# Solar_Charger_Shield_v2_2.net
KiCad netlist of a schematic drawn in EAGLE
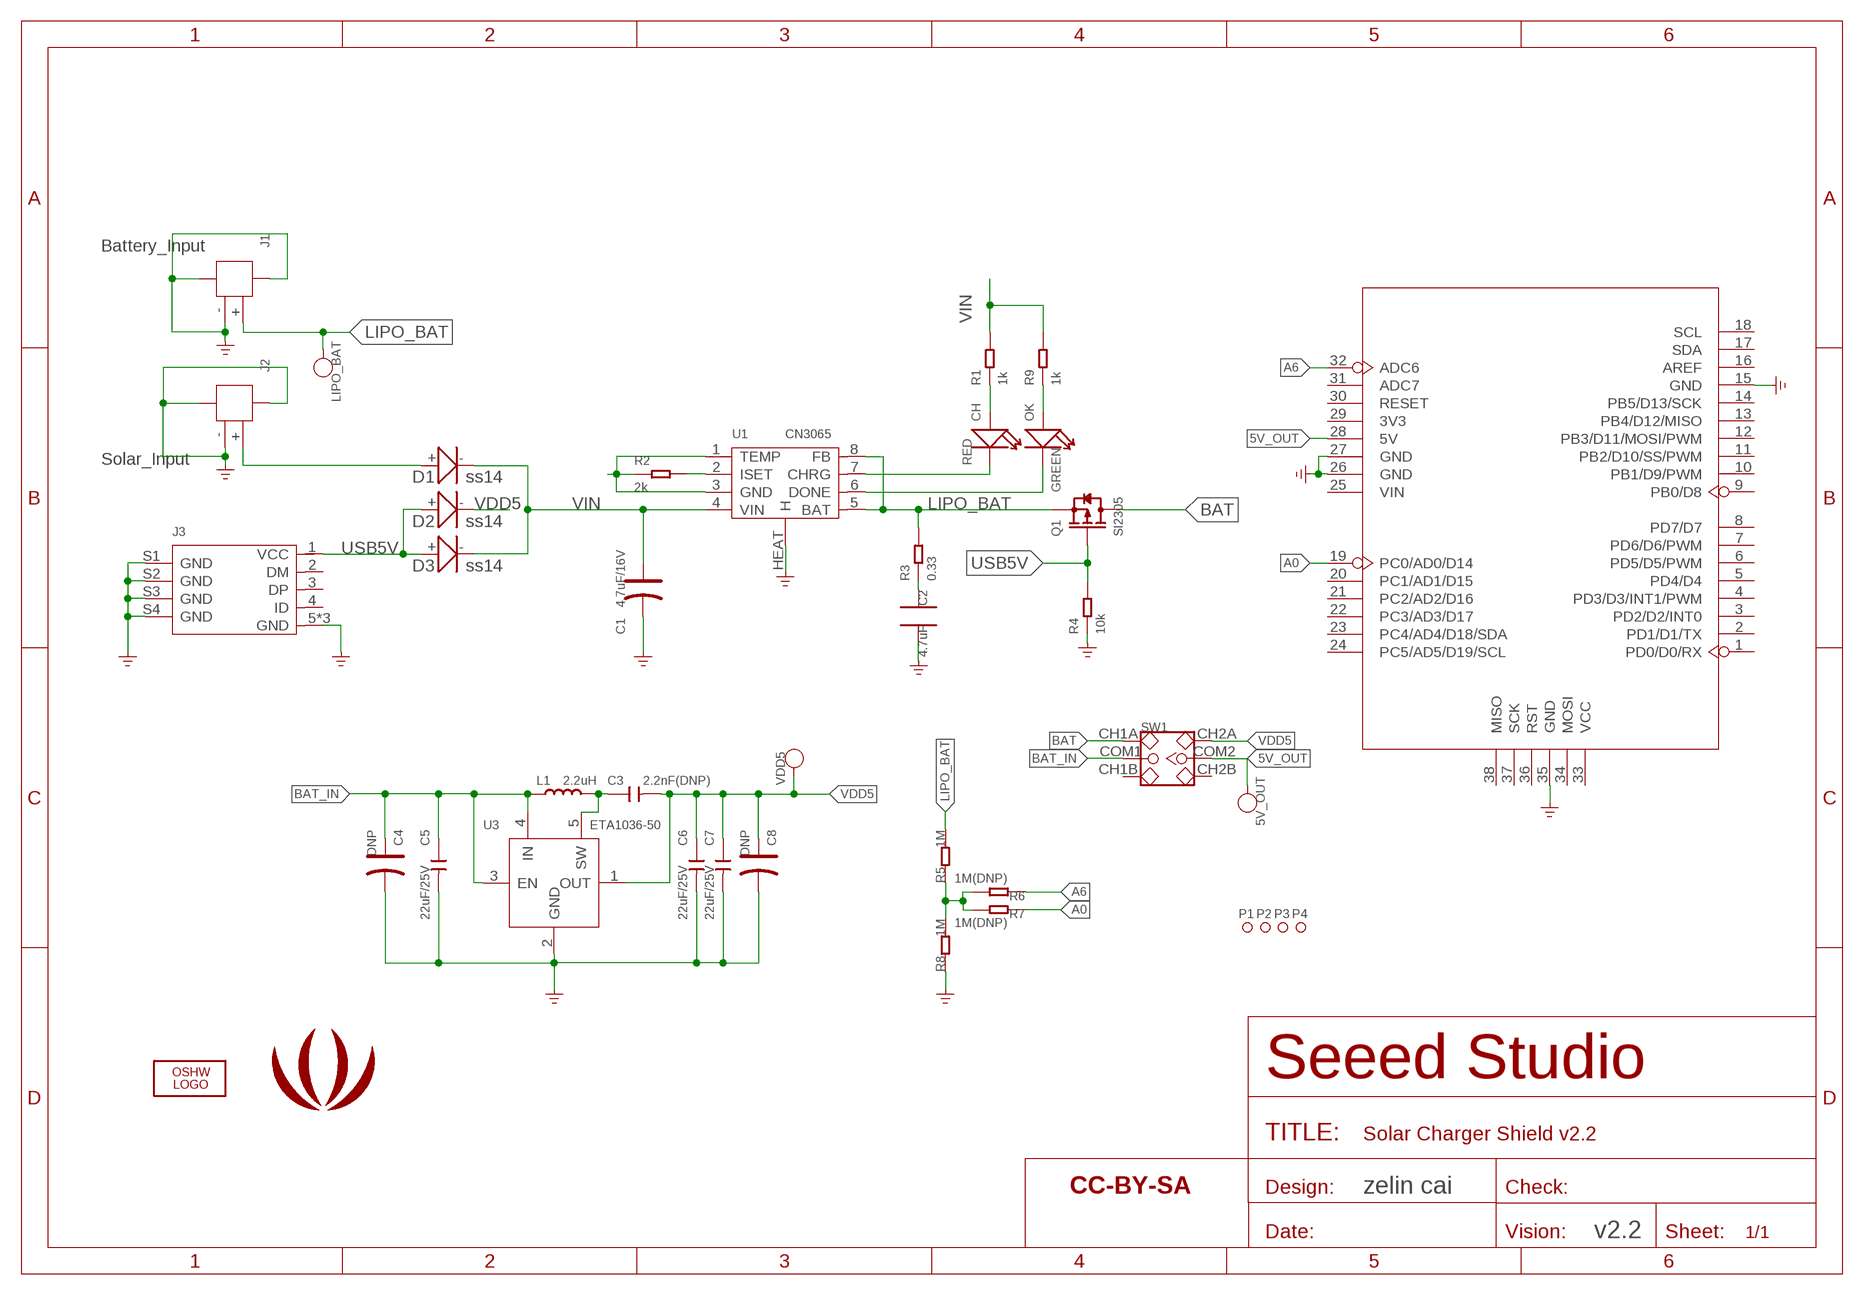
[diagram p0: schematic, sheet 1]

(export (version "E")
  (design (tool "Eeschema 10.0.6"))
  (components
    (comp (ref "5V_OUT")
      (value "PAD-TEST-POINT'4545'")
      (footprint "eagle-import:TP-D45MIL")
      (fields (field (name "PARTNO") "DNP"))
      (libsource (lib "eagle-import") (part "PAD-TEST-POINT'4545'"))
    )
    (comp (ref "C1")
      (value "4.7uF/16V")
      (footprint "eagle-import:AVX_A")
      (libsource (lib "eagle-import") (part "006-CAP_AVX_A"))
    )
    (comp (ref "C2")
      (value "4.7uF")
      (footprint "eagle-import:0805")
      (libsource (lib "eagle-import") (part "C0805"))
    )
    (comp (ref "C3")
      (value "2.2nF(DNP)")
      (footprint "eagle-import:C0603")
      (libsource (lib "eagle-import") (part "C-0603"))
    )
    (comp (ref "C4")
      (value "DNP")
      (footprint "eagle-import:AVX-A")
      (libsource (lib "eagle-import") (part "CAP_AVX_A"))
    )
    (comp (ref "C5")
      (value "22uF/25V")
      (footprint "eagle-import:C0805")
      (libsource (lib "eagle-import") (part "CAP-0805"))
    )
    (comp (ref "C6")
      (value "22uF/25V")
      (footprint "eagle-import:C0805")
      (libsource (lib "eagle-import") (part "CAP-0805"))
    )
    (comp (ref "C7")
      (value "22uF/25V")
      (footprint "eagle-import:C0805")
      (libsource (lib "eagle-import") (part "CAP-0805"))
    )
    (comp (ref "C8")
      (value "DNP")
      (footprint "eagle-import:AVX-A")
      (libsource (lib "eagle-import") (part "CAP_AVX_A"))
    )
    (comp (ref "CH")
      (value "RED")
      (footprint "eagle-import:LED-0603")
      (libsource (lib "eagle-import") (part "LED'0603'"))
    )
    (comp (ref "D1")
      (value "ss14")
      (footprint "eagle-import:D2010")
      (libsource (lib "eagle-import") (part "010-D2010"))
    )
    (comp (ref "D2")
      (value "ss14")
      (footprint "eagle-import:D2010")
      (libsource (lib "eagle-import") (part "010-D2010"))
    )
    (comp (ref "D3")
      (value "ss14")
      (footprint "eagle-import:D2010")
      (libsource (lib "eagle-import") (part "010-D2010"))
    )
    (comp (ref "J1")
      (value "JST-2P-SMD'2.0'")
      (footprint "eagle-import:2P-SMD-2.0-90D")
      (libsource (lib "eagle-import") (part "JST-2P-SMD'2.0'"))
    )
    (comp (ref "J2")
      (value "JST-2P-SMD'2.0'")
      (footprint "eagle-import:2P-SMD-2.0-90D")
      (libsource (lib "eagle-import") (part "JST-2P-SMD'2.0'"))
    )
    (comp (ref "J3")
      (value "USB-MICRO-5P'5+4P'")
      (footprint "eagle-import:5+4P-SMD-0.65-B")
      (libsource (lib "eagle-import") (part "USB-MICRO-5P'5+4P'"))
    )
    (comp (ref "L1")
      (value "2.2uH")
      (footprint "eagle-import:L0630")
      (libsource (lib "eagle-import") (part "INDUCTOR/FERRITE-BEAD'0630'"))
    )
    (comp (ref "LIPO_BAT")
      (value "PAD-TEST-POINT'4545'")
      (footprint "eagle-import:TP-D45MIL")
      (fields (field (name "PARTNO") "DNP"))
      (libsource (lib "eagle-import") (part "PAD-TEST-POINT'4545'"))
    )
    (comp (ref "LOGO1")
      (value "LOGO-OSHW-FILLX0200-NT")
      (footprint "eagle-import:OSHW_FILLX200_NOTEXT")
      (fields (field (name "PARTNO") "DNP"))
      (libsource (lib "eagle-import") (part "LOGO-OSHW-FILLX0200-NT"))
    )
    (comp (ref "OK")
      (value "GREEN")
      (footprint "eagle-import:LED-0603")
      (libsource (lib "eagle-import") (part "LED'0603'"))
    )
    (comp (ref "P1")
      (value "PAD-MARK'ANNULAR'")
      (footprint "eagle-import:ROUND-MARK-1.0")
      (fields (field (name "PARTNO") "DNP"))
      (libsource (lib "eagle-import") (part "PAD-MARK'ANNULAR'"))
    )
    (comp (ref "P2")
      (value "PAD-MARK'ANNULAR'")
      (footprint "eagle-import:ROUND-MARK-1.0")
      (fields (field (name "PARTNO") "DNP"))
      (libsource (lib "eagle-import") (part "PAD-MARK'ANNULAR'"))
    )
    (comp (ref "P3")
      (value "PAD-MARK'ANNULAR'")
      (footprint "eagle-import:ROUND-MARK-1.0")
      (fields (field (name "PARTNO") "DNP"))
      (libsource (lib "eagle-import") (part "PAD-MARK'ANNULAR'"))
    )
    (comp (ref "P4")
      (value "PAD-MARK'ANNULAR'")
      (footprint "eagle-import:ROUND-MARK-1.0")
      (fields (field (name "PARTNO") "DNP"))
      (libsource (lib "eagle-import") (part "PAD-MARK'ANNULAR'"))
    )
    (comp (ref "Q1")
      (value "SI2305")
      (footprint "eagle-import:SOT-23")
      (libsource (lib "eagle-import") (part "MOSFET-P'SI2323CDS/SI2305DS{lt}BR{gt}'"))
    )
    (comp (ref "R1")
      (value "1k")
      (footprint "eagle-import:R0603")
      (libsource (lib "eagle-import") (part "RES-0603"))
    )
    (comp (ref "R2")
      (value "2k")
      (footprint "eagle-import:R0603")
      (libsource (lib "eagle-import") (part "RES-0603"))
    )
    (comp (ref "R3")
      (value "0.33")
      (footprint "eagle-import:R0603")
      (libsource (lib "eagle-import") (part "RES-0603"))
    )
    (comp (ref "R4")
      (value "10k")
      (footprint "eagle-import:R0603")
      (libsource (lib "eagle-import") (part "RES-0603"))
    )
    (comp (ref "R5")
      (value "1M")
      (footprint "eagle-import:0603")
      (libsource (lib "eagle-import") (part "R-0603"))
    )
    (comp (ref "R6")
      (value "1M(DNP)")
      (footprint "eagle-import:0603")
      (libsource (lib "eagle-import") (part "R-0603"))
    )
    (comp (ref "R7")
      (value "1M(DNP)")
      (footprint "eagle-import:0603")
      (libsource (lib "eagle-import") (part "R-0603"))
    )
    (comp (ref "R8")
      (value "1M")
      (footprint "eagle-import:0603")
      (libsource (lib "eagle-import") (part "R-0603"))
    )
    (comp (ref "R9")
      (value "1k")
      (footprint "eagle-import:R0603")
      (libsource (lib "eagle-import") (part "RES-0603"))
    )
    (comp (ref "SW1")
      (value "SWITCH-2CH-6P'90D'")
      (footprint "eagle-import:6P-2CH-2.54-L9.0_W3.5_H3.2-90D")
      (libsource (lib "eagle-import") (part "SWITCH-2CH-6P'90D'"))
    )
    (comp (ref "U$1")
      (value "LOGO-SEEEDSTUDIO-SILK")
      (footprint "eagle-import:LOGO_SILK")
      (libsource (lib "eagle-import") (part "LOGO-SEEEDSTUDIO-SILK"))
    )
    (comp (ref "U$2")
      (value "SEEEDSTUDIO-OPEN-SCH-FRAME")
      (footprint "eagle-import:SEEEDSTUDIO-PCB-FRAME")
      (libsource (lib "eagle-import") (part "SEEEDSTUDIO-OPEN-SCH-FRAME"))
    )
    (comp (ref "U1")
      (value "CN3065")
      (footprint "eagle-import:DFN-8")
      (libsource (lib "eagle-import") (part "PMIC-CN3065-DFN8"))
    )
    (comp (ref "U2")
      (value "ARDUINO-38P'WITH-SILK'")
      (footprint "eagle-import:ARDUINO-DIM-WITH-SILK")
      (libsource (lib "eagle-import") (part "ARDUINO-38P'WITH-SILK'"))
    )
    (comp (ref "U3")
      (value "ETA1036-50")
      (footprint "eagle-import:SOT23-5")
      (libsource (lib "eagle-import") (part "ETA1036"))
    )
    (comp (ref "VDD5")
      (value "PAD-TEST-POINT'4545'")
      (footprint "eagle-import:TP-D45MIL")
      (fields (field (name "PARTNO") "DNP"))
      (libsource (lib "eagle-import") (part "PAD-TEST-POINT'4545'"))
    )
  )
  (nets
    (net (code "1") (name "/VIN") (class "Default")
      (node (ref "C1") (pin "+") (pinfunction "+_+") (pintype "passive"))
      (node (ref "D1") (pin "-") (pinfunction "-_-") (pintype "passive"))
      (node (ref "D3") (pin "-") (pinfunction "-_-") (pintype "passive"))
      (node (ref "R1") (pin "2") (pinfunction "2_2") (pintype "passive"))
      (node (ref "R9") (pin "2") (pinfunction "2_2") (pintype "passive"))
      (node (ref "U1") (pin "4") (pinfunction "VIN_4") (pintype "input"))
    )
    (net (code "2") (name "5V_OUT") (class "Default")
      (node (ref "5V_OUT") (pin "T") (pinfunction "T_T") (pintype "bidirectional"))
      (node (ref "SW1") (pin "COM2") (pinfunction "COM2_COM2") (pintype "bidirectional"))
      (node (ref "U2") (pin "28") (pinfunction "5V_28") (pintype "bidirectional"))
    )
    (net (code "3") (name "A0") (class "Default")
      (node (ref "R7") (pin "1") (pinfunction "1_1") (pintype "passive"))
      (node (ref "U2") (pin "19") (pinfunction "PC0/AD0/D14_19") (pintype "bidirectional"))
    )
    (net (code "4") (name "A6") (class "Default")
      (node (ref "R6") (pin "1") (pinfunction "1_1") (pintype "passive"))
      (node (ref "U2") (pin "32") (pinfunction "ADC6_32") (pintype "bidirectional"))
    )
    (net (code "5") (name "BAT") (class "Default")
      (node (ref "Q1") (pin "3") (pinfunction "D_3") (pintype "passive"))
      (node (ref "SW1") (pin "CH1A") (pinfunction "CH1A_CH1A") (pintype "bidirectional"))
    )
    (net (code "6") (name "BAT_IN") (class "Default")
      (node (ref "C4") (pin "+") (pinfunction "+_+") (pintype "passive"))
      (node (ref "C5") (pin "1") (pinfunction "1_1") (pintype "passive"))
      (node (ref "L1") (pin "1") (pinfunction "1_1") (pintype "passive"))
      (node (ref "SW1") (pin "COM1") (pinfunction "COM1_COM1") (pintype "bidirectional"))
      (node (ref "U3") (pin "3") (pinfunction "EN_3") (pintype "bidirectional"))
      (node (ref "U3") (pin "4") (pinfunction "IN_4") (pintype "bidirectional"))
    )
    (net (code "7") (name "GND_POWER") (class "Default")
      (node (ref "C1") (pin "-") (pinfunction "-_-") (pintype "passive"))
      (node (ref "C2") (pin "2") (pinfunction "2_2") (pintype "bidirectional"))
      (node (ref "C4") (pin "-") (pinfunction "-_-") (pintype "passive"))
      (node (ref "C5") (pin "2") (pinfunction "2_2") (pintype "passive"))
      (node (ref "C6") (pin "2") (pinfunction "2_2") (pintype "passive"))
      (node (ref "C7") (pin "2") (pinfunction "2_2") (pintype "passive"))
      (node (ref "C8") (pin "-") (pinfunction "-_-") (pintype "passive"))
      (node (ref "J1") (pin "-") (pinfunction "2_-") (pintype "bidirectional"))
      (node (ref "J1") (pin "3") (pinfunction "3_3") (pintype "bidirectional"))
      (node (ref "J1") (pin "4") (pinfunction "4_4") (pintype "bidirectional"))
      (node (ref "J2") (pin "-") (pinfunction "2_-") (pintype "bidirectional"))
      (node (ref "J2") (pin "3") (pinfunction "3_3") (pintype "bidirectional"))
      (node (ref "J2") (pin "4") (pinfunction "4_4") (pintype "bidirectional"))
      (node (ref "J3") (pin "5") (pinfunction "GND_5") (pintype "bidirectional"))
      (node (ref "J3") (pin "S1") (pinfunction "GND_S1") (pintype "bidirectional"))
      (node (ref "J3") (pin "S2") (pinfunction "GND_S2") (pintype "bidirectional"))
      (node (ref "J3") (pin "S3") (pinfunction "GND_S3") (pintype "bidirectional"))
      (node (ref "J3") (pin "S4") (pinfunction "GND_S4") (pintype "bidirectional"))
      (node (ref "J3") (pin "S5") (pinfunction "GND_S5") (pintype "bidirectional"))
      (node (ref "J3") (pin "S6") (pinfunction "GND_S6") (pintype "bidirectional"))
      (node (ref "R2") (pin "1") (pinfunction "1_1") (pintype "passive"))
      (node (ref "R4") (pin "1") (pinfunction "1_1") (pintype "passive"))
      (node (ref "R8") (pin "1") (pinfunction "1_1") (pintype "passive"))
      (node (ref "U1") (pin "1") (pinfunction "TEMP_1") (pintype "input"))
      (node (ref "U1") (pin "3") (pinfunction "GND_3") (pintype "power_in"))
      (node (ref "U1") (pin "HEAT") (pinfunction "H_HEAT") (pintype "bidirectional"))
      (node (ref "U2") (pin "15") (pinfunction "GND_15") (pintype "bidirectional"))
      (node (ref "U2") (pin "26") (pinfunction "GND_26") (pintype "bidirectional"))
      (node (ref "U2") (pin "27") (pinfunction "GND_27") (pintype "bidirectional"))
      (node (ref "U2") (pin "35") (pinfunction "GND_35") (pintype "bidirectional"))
      (node (ref "U3") (pin "2") (pinfunction "GND_2") (pintype "bidirectional"))
    )
    (net (code "8") (name "LIPO_BAT") (class "Default")
      (node (ref "J1") (pin "+") (pinfunction "1_+") (pintype "bidirectional"))
      (node (ref "LIPO_BAT") (pin "T") (pinfunction "T_T") (pintype "bidirectional"))
      (node (ref "Q1") (pin "2") (pinfunction "S_2") (pintype "passive"))
      (node (ref "R3") (pin "2") (pinfunction "2_2") (pintype "passive"))
      (node (ref "R5") (pin "2") (pinfunction "2_2") (pintype "passive"))
      (node (ref "U1") (pin "5") (pinfunction "BAT_5") (pintype "bidirectional"))
      (node (ref "U1") (pin "8") (pinfunction "FB_8") (pintype "input"))
    )
    (net (code "9") (name "Net-(C2-Pad1)") (class "Default")
      (node (ref "C2") (pin "1") (pinfunction "1_1") (pintype "bidirectional"))
      (node (ref "R3") (pin "1") (pinfunction "1_1") (pintype "passive"))
    )
    (net (code "10") (name "Net-(CH-Pad+)") (class "Default")
      (node (ref "CH") (pin "+") (pinfunction "+_+") (pintype "passive"))
      (node (ref "R1") (pin "1") (pinfunction "1_1") (pintype "passive"))
    )
    (net (code "11") (name "Net-(J2-1)") (class "Default")
      (node (ref "D1") (pin "+") (pinfunction "+_+") (pintype "passive"))
      (node (ref "J2") (pin "+") (pinfunction "1_+") (pintype "bidirectional"))
    )
    (net (code "12") (name "Net-(OK-Pad+)") (class "Default")
      (node (ref "OK") (pin "+") (pinfunction "+_+") (pintype "passive"))
      (node (ref "R9") (pin "1") (pinfunction "1_1") (pintype "passive"))
    )
    (net (code "13") (name "Net-(R5-Pad1)") (class "Default")
      (node (ref "R5") (pin "1") (pinfunction "1_1") (pintype "passive"))
      (node (ref "R6") (pin "2") (pinfunction "2_2") (pintype "passive"))
      (node (ref "R7") (pin "2") (pinfunction "2_2") (pintype "passive"))
      (node (ref "R8") (pin "2") (pinfunction "2_2") (pintype "passive"))
    )
    (net (code "14") (name "Net-(U1-CHRG)") (class "Default")
      (node (ref "CH") (pin "-") (pinfunction "-_-") (pintype "passive"))
      (node (ref "U1") (pin "7") (pinfunction "CHRG_7") (pintype "bidirectional"))
    )
    (net (code "15") (name "Net-(U1-DONE)") (class "Default")
      (node (ref "OK") (pin "-") (pinfunction "-_-") (pintype "passive"))
      (node (ref "U1") (pin "6") (pinfunction "DONE_6") (pintype "bidirectional"))
    )
    (net (code "16") (name "Net-(U1-ISET)") (class "Default")
      (node (ref "R2") (pin "2") (pinfunction "2_2") (pintype "passive"))
      (node (ref "U1") (pin "2") (pinfunction "ISET_2") (pintype "bidirectional"))
    )
    (net (code "17") (name "Net-(U3-SW)") (class "Default")
      (node (ref "C3") (pin "1") (pinfunction "1_1") (pintype "passive"))
      (node (ref "L1") (pin "2") (pinfunction "2_2") (pintype "passive"))
      (node (ref "U3") (pin "5") (pinfunction "SW_5") (pintype "bidirectional"))
    )
    (net (code "18") (name "USB5V") (class "Default")
      (node (ref "D2") (pin "+") (pinfunction "+_+") (pintype "passive"))
      (node (ref "D3") (pin "+") (pinfunction "+_+") (pintype "passive"))
      (node (ref "J3") (pin "1") (pinfunction "VCC_1") (pintype "bidirectional"))
      (node (ref "Q1") (pin "1") (pinfunction "G_1") (pintype "passive"))
      (node (ref "R4") (pin "2") (pinfunction "2_2") (pintype "passive"))
    )
    (net (code "19") (name "VDD5") (class "Default")
      (node (ref "C3") (pin "2") (pinfunction "2_2") (pintype "passive"))
      (node (ref "C6") (pin "1") (pinfunction "1_1") (pintype "passive"))
      (node (ref "C7") (pin "1") (pinfunction "1_1") (pintype "passive"))
      (node (ref "C8") (pin "+") (pinfunction "+_+") (pintype "passive"))
      (node (ref "D2") (pin "-") (pinfunction "-_-") (pintype "passive"))
      (node (ref "SW1") (pin "CH2A") (pinfunction "CH2A_CH2A") (pintype "bidirectional"))
      (node (ref "U3") (pin "1") (pinfunction "OUT_1") (pintype "bidirectional"))
      (node (ref "VDD5") (pin "T") (pinfunction "T_T") (pintype "bidirectional"))
    )
    (net (code "20") (name "unconnected-(J3-DM-Pad2)") (class "Default")
      (node (ref "J3") (pin "2") (pinfunction "DM_2") (pintype "bidirectional"))
    )
    (net (code "21") (name "unconnected-(J3-DP-Pad3)") (class "Default")
      (node (ref "J3") (pin "3") (pinfunction "DP_3") (pintype "bidirectional"))
    )
    (net (code "22") (name "unconnected-(J3-ID-Pad4)") (class "Default")
      (node (ref "J3") (pin "4") (pinfunction "ID_4") (pintype "bidirectional"))
    )
    (net (code "23") (name "unconnected-(SW1-PadCH1B)") (class "Default")
      (node (ref "SW1") (pin "CH1B") (pinfunction "CH1B_CH1B") (pintype "bidirectional"))
    )
    (net (code "24") (name "unconnected-(SW1-PadCH2B)") (class "Default")
      (node (ref "SW1") (pin "CH2B") (pinfunction "CH2B_CH2B") (pintype "bidirectional"))
    )
    (net (code "25") (name "unconnected-(U2-3V3-Pad29)") (class "Default")
      (node (ref "U2") (pin "29") (pinfunction "3V3_29") (pintype "bidirectional"))
    )
    (net (code "26") (name "unconnected-(U2-ADC7-Pad31)") (class "Default")
      (node (ref "U2") (pin "31") (pinfunction "ADC7_31") (pintype "bidirectional"))
    )
    (net (code "27") (name "unconnected-(U2-AREF-Pad16)") (class "Default")
      (node (ref "U2") (pin "16") (pinfunction "AREF_16") (pintype "bidirectional"))
    )
    (net (code "28") (name "unconnected-(U2-MISO-Pad38)") (class "Default")
      (node (ref "U2") (pin "38") (pinfunction "MISO_38") (pintype "bidirectional"))
    )
    (net (code "29") (name "unconnected-(U2-MOSI-Pad34)") (class "Default")
      (node (ref "U2") (pin "34") (pinfunction "MOSI_34") (pintype "bidirectional"))
    )
    (net (code "30") (name "unconnected-(U2-PB0{slash}D8-Pad9)") (class "Default")
      (node (ref "U2") (pin "9") (pinfunction "PB0/D8_9") (pintype "bidirectional"))
    )
    (net (code "31") (name "unconnected-(U2-PB1{slash}D9{slash}PWM-Pad10)") (class "Default")
      (node (ref "U2") (pin "10") (pinfunction "PB1/D9/PWM_10") (pintype "bidirectional"))
    )
    (net (code "32") (name "unconnected-(U2-PB2{slash}D10{slash}SS{slash}PWM-Pad11)") (class "Default")
      (node (ref "U2") (pin "11") (pinfunction "PB2/D10/SS/PWM_11") (pintype "bidirectional"))
    )
    (net (code "33") (name "unconnected-(U2-PB3{slash}D11{slash}MOSI{slash}PWM-Pad12)") (class "Default")
      (node (ref "U2") (pin "12") (pinfunction "PB3/D11/MOSI/PWM_12") (pintype "bidirectional"))
    )
    (net (code "34") (name "unconnected-(U2-PB4{slash}D12{slash}MISO-Pad13)") (class "Default")
      (node (ref "U2") (pin "13") (pinfunction "PB4/D12/MISO_13") (pintype "bidirectional"))
    )
    (net (code "35") (name "unconnected-(U2-PB5{slash}D13{slash}SCK-Pad14)") (class "Default")
      (node (ref "U2") (pin "14") (pinfunction "PB5/D13/SCK_14") (pintype "bidirectional"))
    )
    (net (code "36") (name "unconnected-(U2-PC1{slash}AD1{slash}D15-Pad20)") (class "Default")
      (node (ref "U2") (pin "20") (pinfunction "PC1/AD1/D15_20") (pintype "bidirectional"))
    )
    (net (code "37") (name "unconnected-(U2-PC2{slash}AD2{slash}D16-Pad21)") (class "Default")
      (node (ref "U2") (pin "21") (pinfunction "PC2/AD2/D16_21") (pintype "bidirectional"))
    )
    (net (code "38") (name "unconnected-(U2-PC3{slash}AD3{slash}D17-Pad22)") (class "Default")
      (node (ref "U2") (pin "22") (pinfunction "PC3/AD3/D17_22") (pintype "bidirectional"))
    )
    (net (code "39") (name "unconnected-(U2-PC4{slash}AD4{slash}D18{slash}SDA-Pad23)") (class "Default")
      (node (ref "U2") (pin "23") (pinfunction "PC4/AD4/D18/SDA_23") (pintype "bidirectional"))
    )
    (net (code "40") (name "unconnected-(U2-PC5{slash}AD5{slash}D19{slash}SCL-Pad24)") (class "Default")
      (node (ref "U2") (pin "24") (pinfunction "PC5/AD5/D19/SCL_24") (pintype "bidirectional"))
    )
    (net (code "41") (name "unconnected-(U2-PD0{slash}D0{slash}RX-Pad1)") (class "Default")
      (node (ref "U2") (pin "1") (pinfunction "PD0/D0/RX_1") (pintype "bidirectional"))
    )
    (net (code "42") (name "unconnected-(U2-PD1{slash}D1{slash}TX-Pad2)") (class "Default")
      (node (ref "U2") (pin "2") (pinfunction "PD1/D1/TX_2") (pintype "bidirectional"))
    )
    (net (code "43") (name "unconnected-(U2-PD2{slash}D2{slash}INT0-Pad3)") (class "Default")
      (node (ref "U2") (pin "3") (pinfunction "PD2/D2/INT0_3") (pintype "bidirectional"))
    )
    (net (code "44") (name "unconnected-(U2-PD3{slash}D3{slash}INT1{slash}PWM-Pad4)") (class "Default")
      (node (ref "U2") (pin "4") (pinfunction "PD3/D3/INT1/PWM_4") (pintype "bidirectional"))
    )
    (net (code "45") (name "unconnected-(U2-PD4{slash}D4-Pad5)") (class "Default")
      (node (ref "U2") (pin "5") (pinfunction "PD4/D4_5") (pintype "bidirectional"))
    )
    (net (code "46") (name "unconnected-(U2-PD5{slash}D5{slash}PWM-Pad6)") (class "Default")
      (node (ref "U2") (pin "6") (pinfunction "PD5/D5/PWM_6") (pintype "bidirectional"))
    )
    (net (code "47") (name "unconnected-(U2-PD6{slash}D6{slash}PWM-Pad7)") (class "Default")
      (node (ref "U2") (pin "7") (pinfunction "PD6/D6/PWM_7") (pintype "bidirectional"))
    )
    (net (code "48") (name "unconnected-(U2-PD7{slash}D7-Pad8)") (class "Default")
      (node (ref "U2") (pin "8") (pinfunction "PD7/D7_8") (pintype "bidirectional"))
    )
    (net (code "49") (name "unconnected-(U2-RESET-Pad30)") (class "Default")
      (node (ref "U2") (pin "30") (pinfunction "RESET_30") (pintype "bidirectional"))
    )
    (net (code "50") (name "unconnected-(U2-RST-Pad36)") (class "Default")
      (node (ref "U2") (pin "36") (pinfunction "RST_36") (pintype "bidirectional"))
    )
    (net (code "51") (name "unconnected-(U2-SCK-Pad37)") (class "Default")
      (node (ref "U2") (pin "37") (pinfunction "SCK_37") (pintype "bidirectional"))
    )
    (net (code "52") (name "unconnected-(U2-SCL-Pad18)") (class "Default")
      (node (ref "U2") (pin "18") (pinfunction "SCL_18") (pintype "bidirectional"))
    )
    (net (code "53") (name "unconnected-(U2-SDA-Pad17)") (class "Default")
      (node (ref "U2") (pin "17") (pinfunction "SDA_17") (pintype "bidirectional"))
    )
    (net (code "54") (name "unconnected-(U2-VCC-Pad33)") (class "Default")
      (node (ref "U2") (pin "33") (pinfunction "VCC_33") (pintype "bidirectional"))
    )
    (net (code "55") (name "unconnected-(U2-VIN-Pad25)") (class "Default")
      (node (ref "U2") (pin "25") (pinfunction "VIN_25") (pintype "bidirectional"))
    )
  )
)
